# support_mega_2560_R3_-_sh_matics.net
KiCad netlist of a schematic drawn in EasyEDA
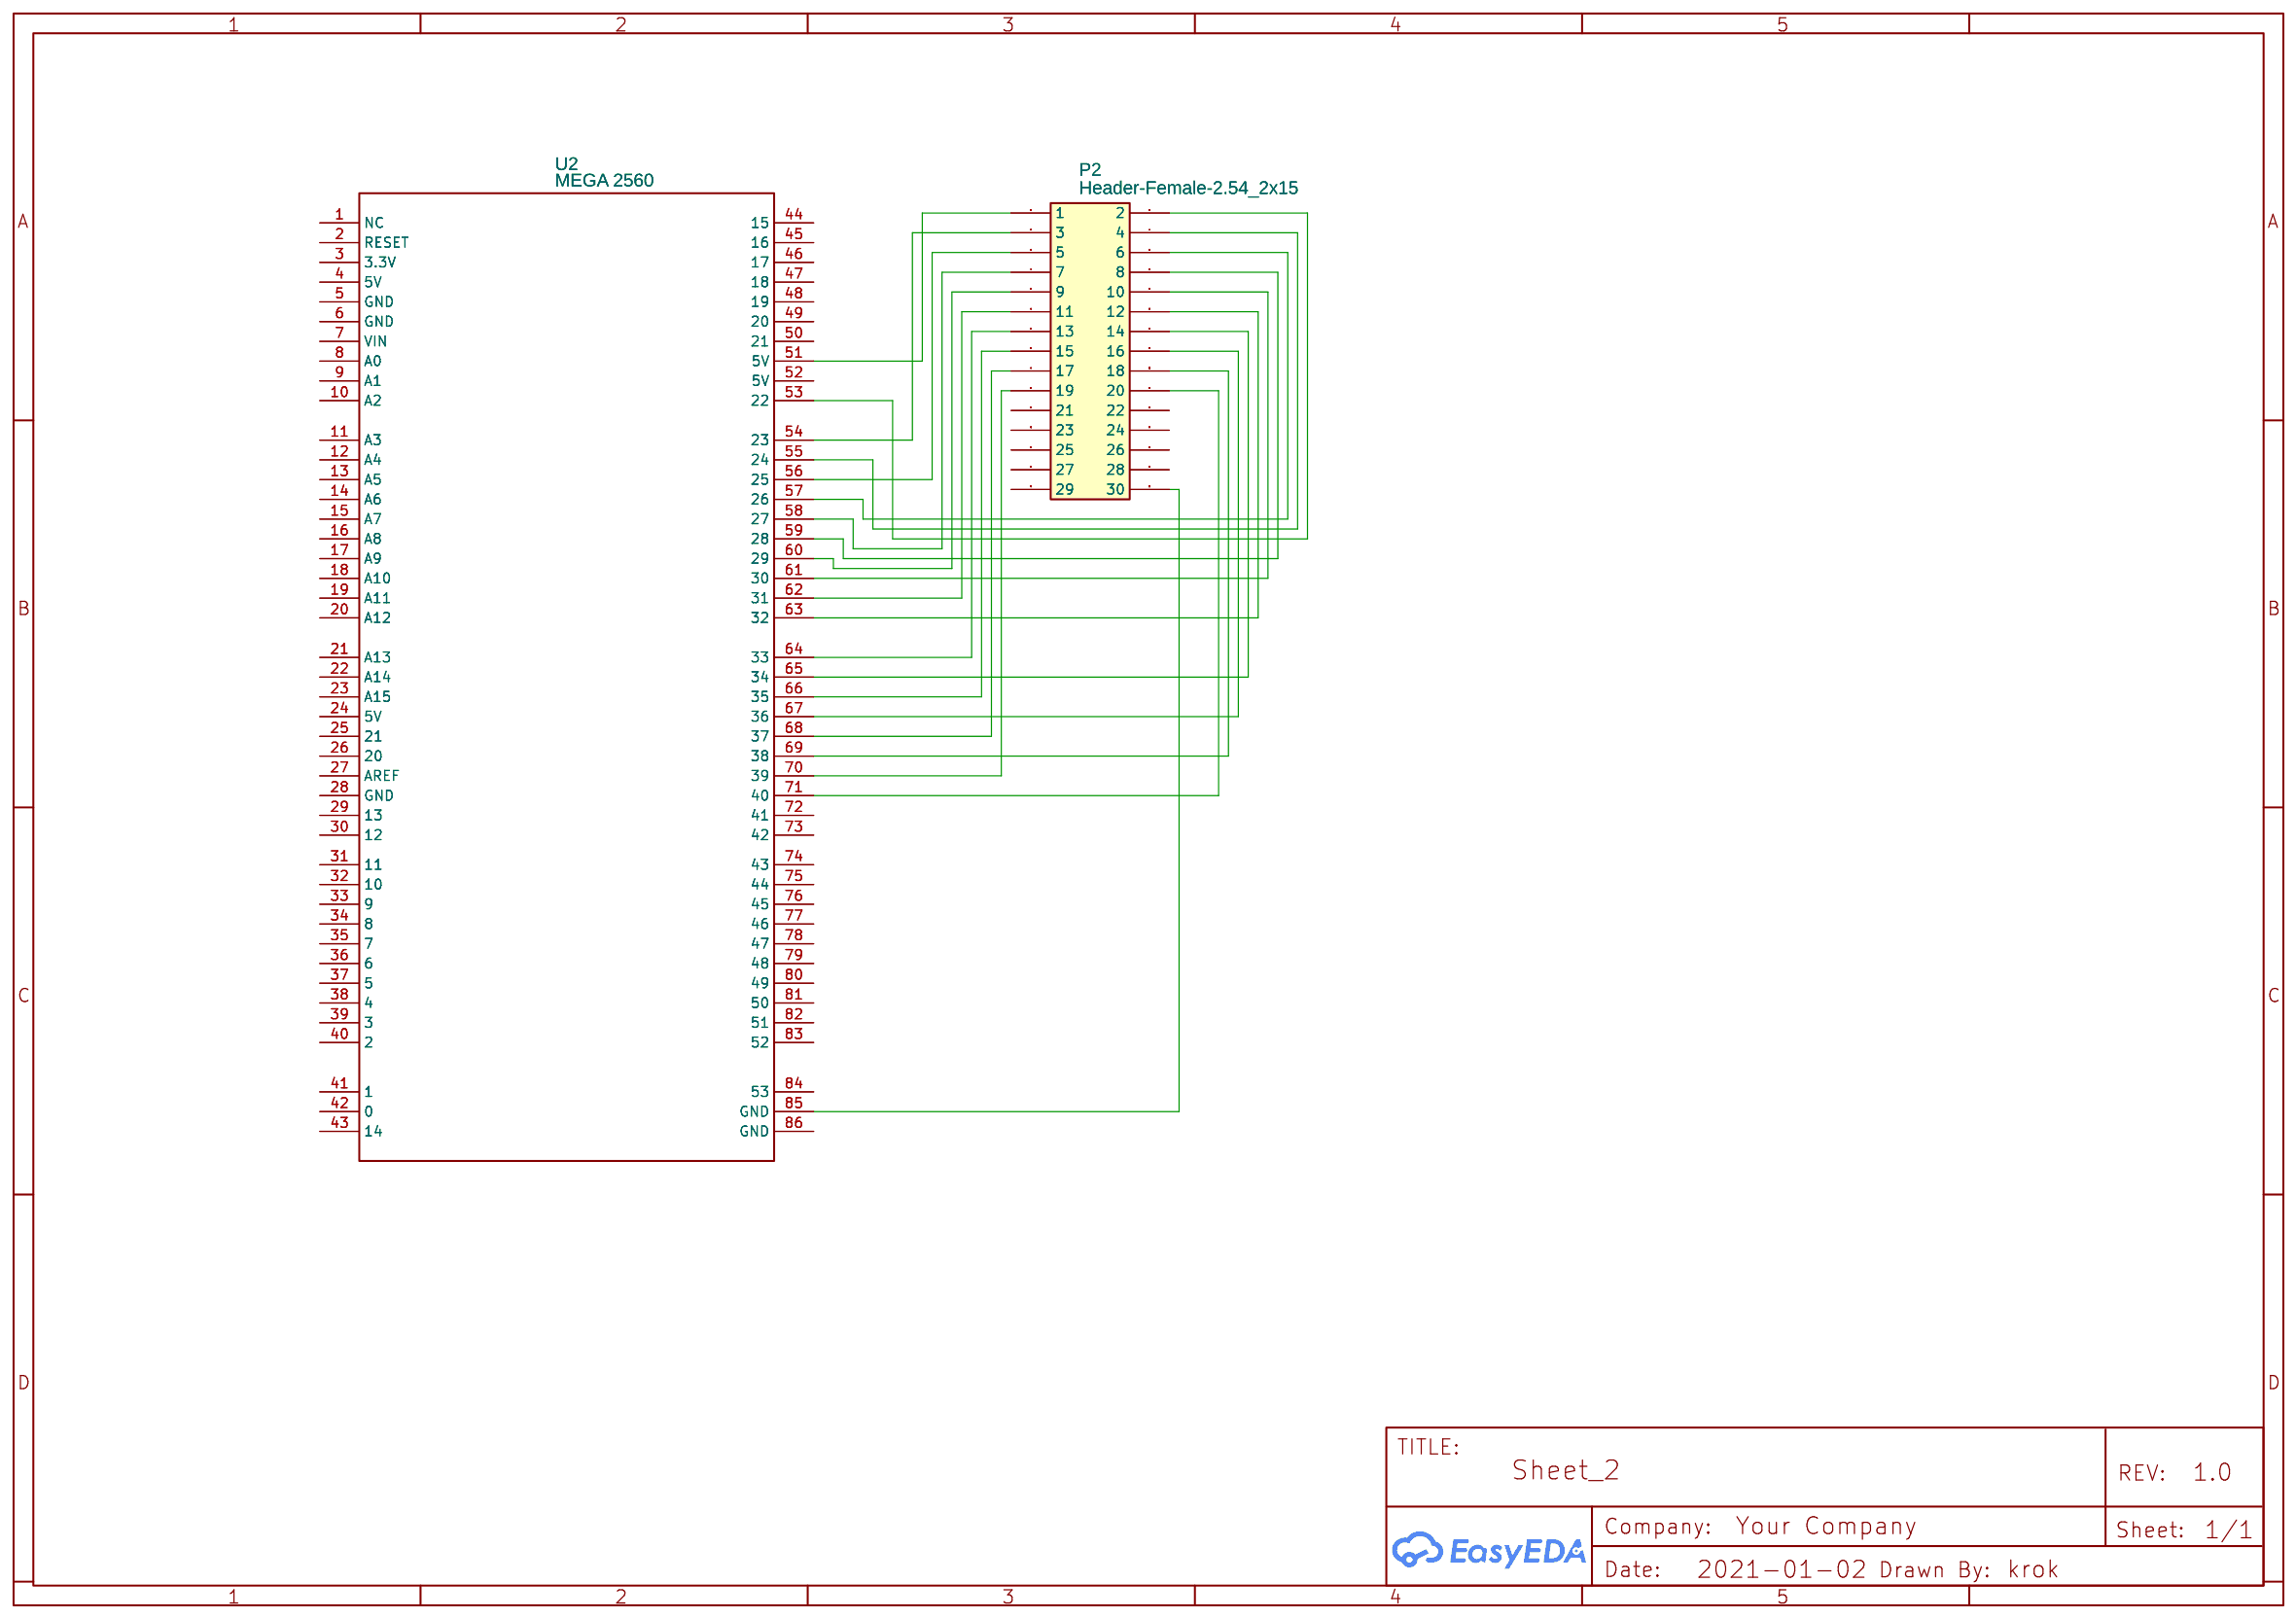
[diagram p0: schematic sheet]

(export (version "E")
  (design (tool "Eeschema 10.0.6"))
  (components
    (comp (ref "P2")
      (value "Header-Female-2.54_2x15")
      (fields (field (name "BOM_Supplier Part") "E58377"))
      (libsource (lib "") (part "Header-Female-2.54_2x15"))
    )
    (comp (ref "U2") (value "MEGA 2560") (libsource (lib "") (part "MEGA 2560")))
  )
  (nets
    (net (code "1") (name "Net-(P2-Pad1)") (class "Default")
      (node (ref "P2") (pin "1") (pinfunction "1_1") (pintype "input"))
      (node (ref "U2") (pin "51") (pinfunction "5V_51") (pintype "unspecified"))
    )
    (net (code "2") (name "Net-(P2-Pad30)") (class "Default")
      (node (ref "P2") (pin "30") (pinfunction "30_30") (pintype "input"))
      (node (ref "U2") (pin "85") (pinfunction "GND_85") (pintype "unspecified"))
    )
    (net (code "3") (name "Net-(U2-22)") (class "Default")
      (node (ref "P2") (pin "2") (pinfunction "2_2") (pintype "input"))
      (node (ref "U2") (pin "53") (pinfunction "22_53") (pintype "unspecified"))
    )
    (net (code "4") (name "Net-(U2-23)") (class "Default")
      (node (ref "P2") (pin "3") (pinfunction "3_3") (pintype "input"))
      (node (ref "U2") (pin "54") (pinfunction "23_54") (pintype "unspecified"))
    )
    (net (code "5") (name "Net-(U2-24)") (class "Default")
      (node (ref "P2") (pin "4") (pinfunction "4_4") (pintype "input"))
      (node (ref "U2") (pin "55") (pinfunction "24_55") (pintype "unspecified"))
    )
    (net (code "6") (name "Net-(U2-25)") (class "Default")
      (node (ref "P2") (pin "5") (pinfunction "5_5") (pintype "input"))
      (node (ref "U2") (pin "56") (pinfunction "25_56") (pintype "unspecified"))
    )
    (net (code "7") (name "Net-(U2-26)") (class "Default")
      (node (ref "P2") (pin "6") (pinfunction "6_6") (pintype "input"))
      (node (ref "U2") (pin "57") (pinfunction "26_57") (pintype "unspecified"))
    )
    (net (code "8") (name "Net-(U2-27)") (class "Default")
      (node (ref "P2") (pin "7") (pinfunction "7_7") (pintype "input"))
      (node (ref "U2") (pin "58") (pinfunction "27_58") (pintype "unspecified"))
    )
    (net (code "9") (name "Net-(U2-28)") (class "Default")
      (node (ref "P2") (pin "8") (pinfunction "8_8") (pintype "input"))
      (node (ref "U2") (pin "59") (pinfunction "28_59") (pintype "unspecified"))
    )
    (net (code "10") (name "Net-(U2-29)") (class "Default")
      (node (ref "P2") (pin "9") (pinfunction "9_9") (pintype "input"))
      (node (ref "U2") (pin "60") (pinfunction "29_60") (pintype "unspecified"))
    )
    (net (code "11") (name "Net-(U2-30)") (class "Default")
      (node (ref "P2") (pin "10") (pinfunction "10_10") (pintype "input"))
      (node (ref "U2") (pin "61") (pinfunction "30_61") (pintype "unspecified"))
    )
    (net (code "12") (name "Net-(U2-31)") (class "Default")
      (node (ref "P2") (pin "11") (pinfunction "11_11") (pintype "input"))
      (node (ref "U2") (pin "62") (pinfunction "31_62") (pintype "unspecified"))
    )
    (net (code "13") (name "Net-(U2-32)") (class "Default")
      (node (ref "P2") (pin "12") (pinfunction "12_12") (pintype "input"))
      (node (ref "U2") (pin "63") (pinfunction "32_63") (pintype "unspecified"))
    )
    (net (code "14") (name "Net-(U2-33)") (class "Default")
      (node (ref "P2") (pin "13") (pinfunction "13_13") (pintype "input"))
      (node (ref "U2") (pin "64") (pinfunction "33_64") (pintype "unspecified"))
    )
    (net (code "15") (name "Net-(U2-34)") (class "Default")
      (node (ref "P2") (pin "14") (pinfunction "14_14") (pintype "input"))
      (node (ref "U2") (pin "65") (pinfunction "34_65") (pintype "unspecified"))
    )
    (net (code "16") (name "Net-(U2-35)") (class "Default")
      (node (ref "P2") (pin "15") (pinfunction "15_15") (pintype "input"))
      (node (ref "U2") (pin "66") (pinfunction "35_66") (pintype "unspecified"))
    )
    (net (code "17") (name "Net-(U2-36)") (class "Default")
      (node (ref "P2") (pin "16") (pinfunction "16_16") (pintype "input"))
      (node (ref "U2") (pin "67") (pinfunction "36_67") (pintype "unspecified"))
    )
    (net (code "18") (name "Net-(U2-37)") (class "Default")
      (node (ref "P2") (pin "17") (pinfunction "17_17") (pintype "input"))
      (node (ref "U2") (pin "68") (pinfunction "37_68") (pintype "unspecified"))
    )
    (net (code "19") (name "Net-(U2-38)") (class "Default")
      (node (ref "P2") (pin "18") (pinfunction "18_18") (pintype "input"))
      (node (ref "U2") (pin "69") (pinfunction "38_69") (pintype "unspecified"))
    )
    (net (code "20") (name "Net-(U2-39)") (class "Default")
      (node (ref "P2") (pin "19") (pinfunction "19_19") (pintype "input"))
      (node (ref "U2") (pin "70") (pinfunction "39_70") (pintype "unspecified"))
    )
    (net (code "21") (name "Net-(U2-40)") (class "Default")
      (node (ref "P2") (pin "20") (pinfunction "20_20") (pintype "input"))
      (node (ref "U2") (pin "71") (pinfunction "40_71") (pintype "unspecified"))
    )
    (net (code "22") (name "unconnected-(P2-Pad21)") (class "Default")
      (node (ref "P2") (pin "21") (pinfunction "21_21") (pintype "input"))
    )
    (net (code "23") (name "unconnected-(P2-Pad22)") (class "Default")
      (node (ref "P2") (pin "22") (pinfunction "22_22") (pintype "input"))
    )
    (net (code "24") (name "unconnected-(P2-Pad23)") (class "Default")
      (node (ref "P2") (pin "23") (pinfunction "23_23") (pintype "input"))
    )
    (net (code "25") (name "unconnected-(P2-Pad24)") (class "Default")
      (node (ref "P2") (pin "24") (pinfunction "24_24") (pintype "input"))
    )
    (net (code "26") (name "unconnected-(P2-Pad25)") (class "Default")
      (node (ref "P2") (pin "25") (pinfunction "25_25") (pintype "input"))
    )
    (net (code "27") (name "unconnected-(P2-Pad26)") (class "Default")
      (node (ref "P2") (pin "26") (pinfunction "26_26") (pintype "input"))
    )
    (net (code "28") (name "unconnected-(P2-Pad27)") (class "Default")
      (node (ref "P2") (pin "27") (pinfunction "27_27") (pintype "input"))
    )
    (net (code "29") (name "unconnected-(P2-Pad28)") (class "Default")
      (node (ref "P2") (pin "28") (pinfunction "28_28") (pintype "input"))
    )
    (net (code "30") (name "unconnected-(P2-Pad29)") (class "Default")
      (node (ref "P2") (pin "29") (pinfunction "29_29") (pintype "input"))
    )
    (net (code "31") (name "unconnected-(U2-0-Pad42)") (class "Default")
      (node (ref "U2") (pin "42") (pinfunction "0_42") (pintype "unspecified"))
    )
    (net (code "32") (name "unconnected-(U2-1-Pad41)") (class "Default")
      (node (ref "U2") (pin "41") (pinfunction "1_41") (pintype "unspecified"))
    )
    (net (code "33") (name "unconnected-(U2-2-Pad40)") (class "Default")
      (node (ref "U2") (pin "40") (pinfunction "2_40") (pintype "unspecified"))
    )
    (net (code "34") (name "unconnected-(U2-3-Pad39)") (class "Default")
      (node (ref "U2") (pin "39") (pinfunction "3_39") (pintype "unspecified"))
    )
    (net (code "35") (name "unconnected-(U2-3.3V-Pad3)") (class "Default")
      (node (ref "U2") (pin "3") (pinfunction "3.3V_3") (pintype "unspecified"))
    )
    (net (code "36") (name "unconnected-(U2-4-Pad38)") (class "Default")
      (node (ref "U2") (pin "38") (pinfunction "4_38") (pintype "unspecified"))
    )
    (net (code "37") (name "unconnected-(U2-5-Pad37)") (class "Default")
      (node (ref "U2") (pin "37") (pinfunction "5_37") (pintype "unspecified"))
    )
    (net (code "38") (name "unconnected-(U2-5V-Pad4)") (class "Default")
      (node (ref "U2") (pin "4") (pinfunction "5V_4") (pintype "unspecified"))
    )
    (net (code "39") (name "unconnected-(U2-5V-Pad24)") (class "Default")
      (node (ref "U2") (pin "24") (pinfunction "5V_24") (pintype "unspecified"))
    )
    (net (code "40") (name "unconnected-(U2-5V-Pad52)") (class "Default")
      (node (ref "U2") (pin "52") (pinfunction "5V_52") (pintype "unspecified"))
    )
    (net (code "41") (name "unconnected-(U2-6-Pad36)") (class "Default")
      (node (ref "U2") (pin "36") (pinfunction "6_36") (pintype "unspecified"))
    )
    (net (code "42") (name "unconnected-(U2-7-Pad35)") (class "Default")
      (node (ref "U2") (pin "35") (pinfunction "7_35") (pintype "unspecified"))
    )
    (net (code "43") (name "unconnected-(U2-8-Pad34)") (class "Default")
      (node (ref "U2") (pin "34") (pinfunction "8_34") (pintype "unspecified"))
    )
    (net (code "44") (name "unconnected-(U2-9-Pad33)") (class "Default")
      (node (ref "U2") (pin "33") (pinfunction "9_33") (pintype "unspecified"))
    )
    (net (code "45") (name "unconnected-(U2-10-Pad32)") (class "Default")
      (node (ref "U2") (pin "32") (pinfunction "10_32") (pintype "unspecified"))
    )
    (net (code "46") (name "unconnected-(U2-11-Pad31)") (class "Default")
      (node (ref "U2") (pin "31") (pinfunction "11_31") (pintype "unspecified"))
    )
    (net (code "47") (name "unconnected-(U2-12-Pad30)") (class "Default")
      (node (ref "U2") (pin "30") (pinfunction "12_30") (pintype "unspecified"))
    )
    (net (code "48") (name "unconnected-(U2-13-Pad29)") (class "Default")
      (node (ref "U2") (pin "29") (pinfunction "13_29") (pintype "unspecified"))
    )
    (net (code "49") (name "unconnected-(U2-14-Pad43)") (class "Default")
      (node (ref "U2") (pin "43") (pinfunction "14_43") (pintype "unspecified"))
    )
    (net (code "50") (name "unconnected-(U2-15-Pad44)") (class "Default")
      (node (ref "U2") (pin "44") (pinfunction "15_44") (pintype "unspecified"))
    )
    (net (code "51") (name "unconnected-(U2-16-Pad45)") (class "Default")
      (node (ref "U2") (pin "45") (pinfunction "16_45") (pintype "unspecified"))
    )
    (net (code "52") (name "unconnected-(U2-17-Pad46)") (class "Default")
      (node (ref "U2") (pin "46") (pinfunction "17_46") (pintype "unspecified"))
    )
    (net (code "53") (name "unconnected-(U2-18-Pad47)") (class "Default")
      (node (ref "U2") (pin "47") (pinfunction "18_47") (pintype "unspecified"))
    )
    (net (code "54") (name "unconnected-(U2-19-Pad48)") (class "Default")
      (node (ref "U2") (pin "48") (pinfunction "19_48") (pintype "unspecified"))
    )
    (net (code "55") (name "unconnected-(U2-20-Pad26)") (class "Default")
      (node (ref "U2") (pin "26") (pinfunction "20_26") (pintype "unspecified"))
    )
    (net (code "56") (name "unconnected-(U2-20-Pad49)") (class "Default")
      (node (ref "U2") (pin "49") (pinfunction "20_49") (pintype "unspecified"))
    )
    (net (code "57") (name "unconnected-(U2-21-Pad25)") (class "Default")
      (node (ref "U2") (pin "25") (pinfunction "21_25") (pintype "unspecified"))
    )
    (net (code "58") (name "unconnected-(U2-21-Pad50)") (class "Default")
      (node (ref "U2") (pin "50") (pinfunction "21_50") (pintype "unspecified"))
    )
    (net (code "59") (name "unconnected-(U2-41-Pad72)") (class "Default")
      (node (ref "U2") (pin "72") (pinfunction "41_72") (pintype "unspecified"))
    )
    (net (code "60") (name "unconnected-(U2-42-Pad73)") (class "Default")
      (node (ref "U2") (pin "73") (pinfunction "42_73") (pintype "unspecified"))
    )
    (net (code "61") (name "unconnected-(U2-43-Pad74)") (class "Default")
      (node (ref "U2") (pin "74") (pinfunction "43_74") (pintype "unspecified"))
    )
    (net (code "62") (name "unconnected-(U2-44-Pad75)") (class "Default")
      (node (ref "U2") (pin "75") (pinfunction "44_75") (pintype "unspecified"))
    )
    (net (code "63") (name "unconnected-(U2-45-Pad76)") (class "Default")
      (node (ref "U2") (pin "76") (pinfunction "45_76") (pintype "unspecified"))
    )
    (net (code "64") (name "unconnected-(U2-46-Pad77)") (class "Default")
      (node (ref "U2") (pin "77") (pinfunction "46_77") (pintype "unspecified"))
    )
    (net (code "65") (name "unconnected-(U2-47-Pad78)") (class "Default")
      (node (ref "U2") (pin "78") (pinfunction "47_78") (pintype "unspecified"))
    )
    (net (code "66") (name "unconnected-(U2-48-Pad79)") (class "Default")
      (node (ref "U2") (pin "79") (pinfunction "48_79") (pintype "unspecified"))
    )
    (net (code "67") (name "unconnected-(U2-49-Pad80)") (class "Default")
      (node (ref "U2") (pin "80") (pinfunction "49_80") (pintype "unspecified"))
    )
    (net (code "68") (name "unconnected-(U2-50-Pad81)") (class "Default")
      (node (ref "U2") (pin "81") (pinfunction "50_81") (pintype "unspecified"))
    )
    (net (code "69") (name "unconnected-(U2-51-Pad82)") (class "Default")
      (node (ref "U2") (pin "82") (pinfunction "51_82") (pintype "unspecified"))
    )
    (net (code "70") (name "unconnected-(U2-52-Pad83)") (class "Default")
      (node (ref "U2") (pin "83") (pinfunction "52_83") (pintype "unspecified"))
    )
    (net (code "71") (name "unconnected-(U2-53-Pad84)") (class "Default")
      (node (ref "U2") (pin "84") (pinfunction "53_84") (pintype "unspecified"))
    )
    (net (code "72") (name "unconnected-(U2-A0-Pad8)") (class "Default")
      (node (ref "U2") (pin "8") (pinfunction "A0_8") (pintype "unspecified"))
    )
    (net (code "73") (name "unconnected-(U2-A1-Pad9)") (class "Default")
      (node (ref "U2") (pin "9") (pinfunction "A1_9") (pintype "unspecified"))
    )
    (net (code "74") (name "unconnected-(U2-A2-Pad10)") (class "Default")
      (node (ref "U2") (pin "10") (pinfunction "A2_10") (pintype "unspecified"))
    )
    (net (code "75") (name "unconnected-(U2-A3-Pad11)") (class "Default")
      (node (ref "U2") (pin "11") (pinfunction "A3_11") (pintype "unspecified"))
    )
    (net (code "76") (name "unconnected-(U2-A4-Pad12)") (class "Default")
      (node (ref "U2") (pin "12") (pinfunction "A4_12") (pintype "unspecified"))
    )
    (net (code "77") (name "unconnected-(U2-A5-Pad13)") (class "Default")
      (node (ref "U2") (pin "13") (pinfunction "A5_13") (pintype "unspecified"))
    )
    (net (code "78") (name "unconnected-(U2-A6-Pad14)") (class "Default")
      (node (ref "U2") (pin "14") (pinfunction "A6_14") (pintype "unspecified"))
    )
    (net (code "79") (name "unconnected-(U2-A7-Pad15)") (class "Default")
      (node (ref "U2") (pin "15") (pinfunction "A7_15") (pintype "unspecified"))
    )
    (net (code "80") (name "unconnected-(U2-A8-Pad16)") (class "Default")
      (node (ref "U2") (pin "16") (pinfunction "A8_16") (pintype "unspecified"))
    )
    (net (code "81") (name "unconnected-(U2-A9-Pad17)") (class "Default")
      (node (ref "U2") (pin "17") (pinfunction "A9_17") (pintype "unspecified"))
    )
    (net (code "82") (name "unconnected-(U2-A10-Pad18)") (class "Default")
      (node (ref "U2") (pin "18") (pinfunction "A10_18") (pintype "unspecified"))
    )
    (net (code "83") (name "unconnected-(U2-A11-Pad19)") (class "Default")
      (node (ref "U2") (pin "19") (pinfunction "A11_19") (pintype "unspecified"))
    )
    (net (code "84") (name "unconnected-(U2-A12-Pad20)") (class "Default")
      (node (ref "U2") (pin "20") (pinfunction "A12_20") (pintype "unspecified"))
    )
    (net (code "85") (name "unconnected-(U2-A13-Pad21)") (class "Default")
      (node (ref "U2") (pin "21") (pinfunction "A13_21") (pintype "unspecified"))
    )
    (net (code "86") (name "unconnected-(U2-A14-Pad22)") (class "Default")
      (node (ref "U2") (pin "22") (pinfunction "A14_22") (pintype "unspecified"))
    )
    (net (code "87") (name "unconnected-(U2-A15-Pad23)") (class "Default")
      (node (ref "U2") (pin "23") (pinfunction "A15_23") (pintype "unspecified"))
    )
    (net (code "88") (name "unconnected-(U2-AREF-Pad27)") (class "Default")
      (node (ref "U2") (pin "27") (pinfunction "AREF_27") (pintype "unspecified"))
    )
    (net (code "89") (name "unconnected-(U2-GND-Pad5)") (class "Default")
      (node (ref "U2") (pin "5") (pinfunction "GND_5") (pintype "unspecified"))
    )
    (net (code "90") (name "unconnected-(U2-GND-Pad6)") (class "Default")
      (node (ref "U2") (pin "6") (pinfunction "GND_6") (pintype "unspecified"))
    )
    (net (code "91") (name "unconnected-(U2-GND-Pad28)") (class "Default")
      (node (ref "U2") (pin "28") (pinfunction "GND_28") (pintype "unspecified"))
    )
    (net (code "92") (name "unconnected-(U2-GND-Pad86)") (class "Default")
      (node (ref "U2") (pin "86") (pinfunction "GND_86") (pintype "unspecified"))
    )
    (net (code "93") (name "unconnected-(U2-NC-Pad1)") (class "Default")
      (node (ref "U2") (pin "1") (pinfunction "NC_1") (pintype "unspecified"))
    )
    (net (code "94") (name "unconnected-(U2-RESET-Pad2)") (class "Default")
      (node (ref "U2") (pin "2") (pinfunction "RESET_2") (pintype "unspecified"))
    )
    (net (code "95") (name "unconnected-(U2-VIN-Pad7)") (class "Default")
      (node (ref "U2") (pin "7") (pinfunction "VIN_7") (pintype "unspecified"))
    )
  )
)
